# Module_20200225_0_Traffic_Light.net
KiCad netlist of a schematic drawn in EAGLE
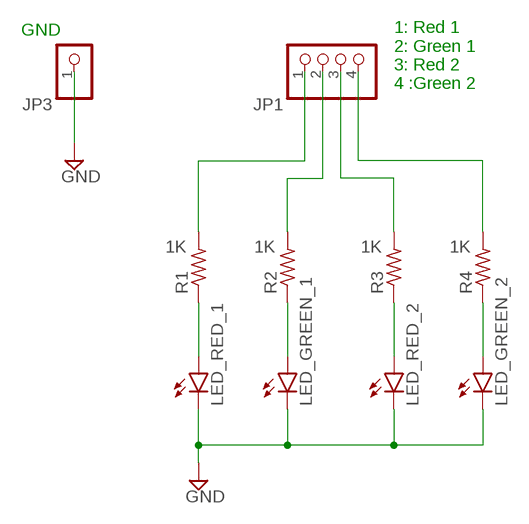
[diagram p0: schematic, sheet 1]

(export (version "E")
  (design (tool "Eeschema 10.0.6"))
  (components
    (comp (ref "JP1")
      (value "PINHD-1X4")
      (footprint "eagle-import:1X04")
      (libsource (lib "eagle-import") (part "PINHD-1X4"))
    )
    (comp (ref "JP3")
      (value "PINHD-1X1")
      (footprint "eagle-import:1X01")
      (libsource (lib "eagle-import") (part "PINHD-1X1"))
    )
    (comp (ref "LED_GREEN_1")
      (value "LAP4-BOTTOM")
      (footprint "eagle-import:P47F-BOTTOM")
      (libsource (lib "eagle-import") (part "P4-BOTTOMLA"))
    )
    (comp (ref "LED_GREEN_2")
      (value "LAP4-BOTTOM")
      (footprint "eagle-import:P47F-BOTTOM")
      (libsource (lib "eagle-import") (part "P4-BOTTOMLA"))
    )
    (comp (ref "LED_RED_1")
      (value "LAP4-BOTTOM")
      (footprint "eagle-import:P47F-BOTTOM")
      (libsource (lib "eagle-import") (part "P4-BOTTOMLA"))
    )
    (comp (ref "LED_RED_2")
      (value "LAP4-BOTTOM")
      (footprint "eagle-import:P47F-BOTTOM")
      (libsource (lib "eagle-import") (part "P4-BOTTOMLA"))
    )
    (comp (ref "R1")
      (value "1K")
      (footprint "eagle-import:0207_5V")
      (libsource (lib "eagle-import") (part "R-US_0207/5V"))
    )
    (comp (ref "R2")
      (value "1K")
      (footprint "eagle-import:0207_5V")
      (libsource (lib "eagle-import") (part "R-US_0207/5V"))
    )
    (comp (ref "R3")
      (value "1K")
      (footprint "eagle-import:0207_5V")
      (libsource (lib "eagle-import") (part "R-US_0207/5V"))
    )
    (comp (ref "R4")
      (value "1K")
      (footprint "eagle-import:0207_5V")
      (libsource (lib "eagle-import") (part "R-US_0207/5V"))
    )
  )
  (nets
    (net (code "1") (name "GND") (class "Default")
      (node (ref "JP3") (pin "1") (pinfunction "1_1") (pintype "passive"))
      (node (ref "LED_GREEN_1") (pin "C") (pinfunction "C_C") (pintype "passive"))
      (node (ref "LED_GREEN_2") (pin "C") (pinfunction "C_C") (pintype "passive"))
      (node (ref "LED_RED_1") (pin "C") (pinfunction "C_C") (pintype "passive"))
      (node (ref "LED_RED_2") (pin "C") (pinfunction "C_C") (pintype "passive"))
    )
    (net (code "2") (name "Net-(JP1-Pad1)") (class "Default")
      (node (ref "JP1") (pin "1") (pinfunction "1_1") (pintype "passive"))
      (node (ref "R1") (pin "2") (pinfunction "2_2") (pintype "passive"))
    )
    (net (code "3") (name "Net-(JP1-Pad2)") (class "Default")
      (node (ref "JP1") (pin "2") (pinfunction "2_2") (pintype "passive"))
      (node (ref "R2") (pin "2") (pinfunction "2_2") (pintype "passive"))
    )
    (net (code "4") (name "Net-(JP1-Pad3)") (class "Default")
      (node (ref "JP1") (pin "3") (pinfunction "3_3") (pintype "passive"))
      (node (ref "R3") (pin "2") (pinfunction "2_2") (pintype "passive"))
    )
    (net (code "5") (name "Net-(JP1-Pad4)") (class "Default")
      (node (ref "JP1") (pin "4") (pinfunction "4_4") (pintype "passive"))
      (node (ref "R4") (pin "2") (pinfunction "2_2") (pintype "passive"))
    )
    (net (code "6") (name "Net-(LED_GREEN_1-PadA)") (class "Default")
      (node (ref "LED_GREEN_1") (pin "A") (pinfunction "A_A") (pintype "passive"))
      (node (ref "R2") (pin "1") (pinfunction "1_1") (pintype "passive"))
    )
    (net (code "7") (name "Net-(LED_GREEN_2-PadA)") (class "Default")
      (node (ref "LED_GREEN_2") (pin "A") (pinfunction "A_A") (pintype "passive"))
      (node (ref "R4") (pin "1") (pinfunction "1_1") (pintype "passive"))
    )
    (net (code "8") (name "Net-(LED_RED_1-PadA)") (class "Default")
      (node (ref "LED_RED_1") (pin "A") (pinfunction "A_A") (pintype "passive"))
      (node (ref "R1") (pin "1") (pinfunction "1_1") (pintype "passive"))
    )
    (net (code "9") (name "Net-(LED_RED_2-PadA)") (class "Default")
      (node (ref "LED_RED_2") (pin "A") (pinfunction "A_A") (pintype "passive"))
      (node (ref "R3") (pin "1") (pinfunction "1_1") (pintype "passive"))
    )
  )
)
